# mainpcb.net
KiCad netlist of a schematic drawn in EAGLE
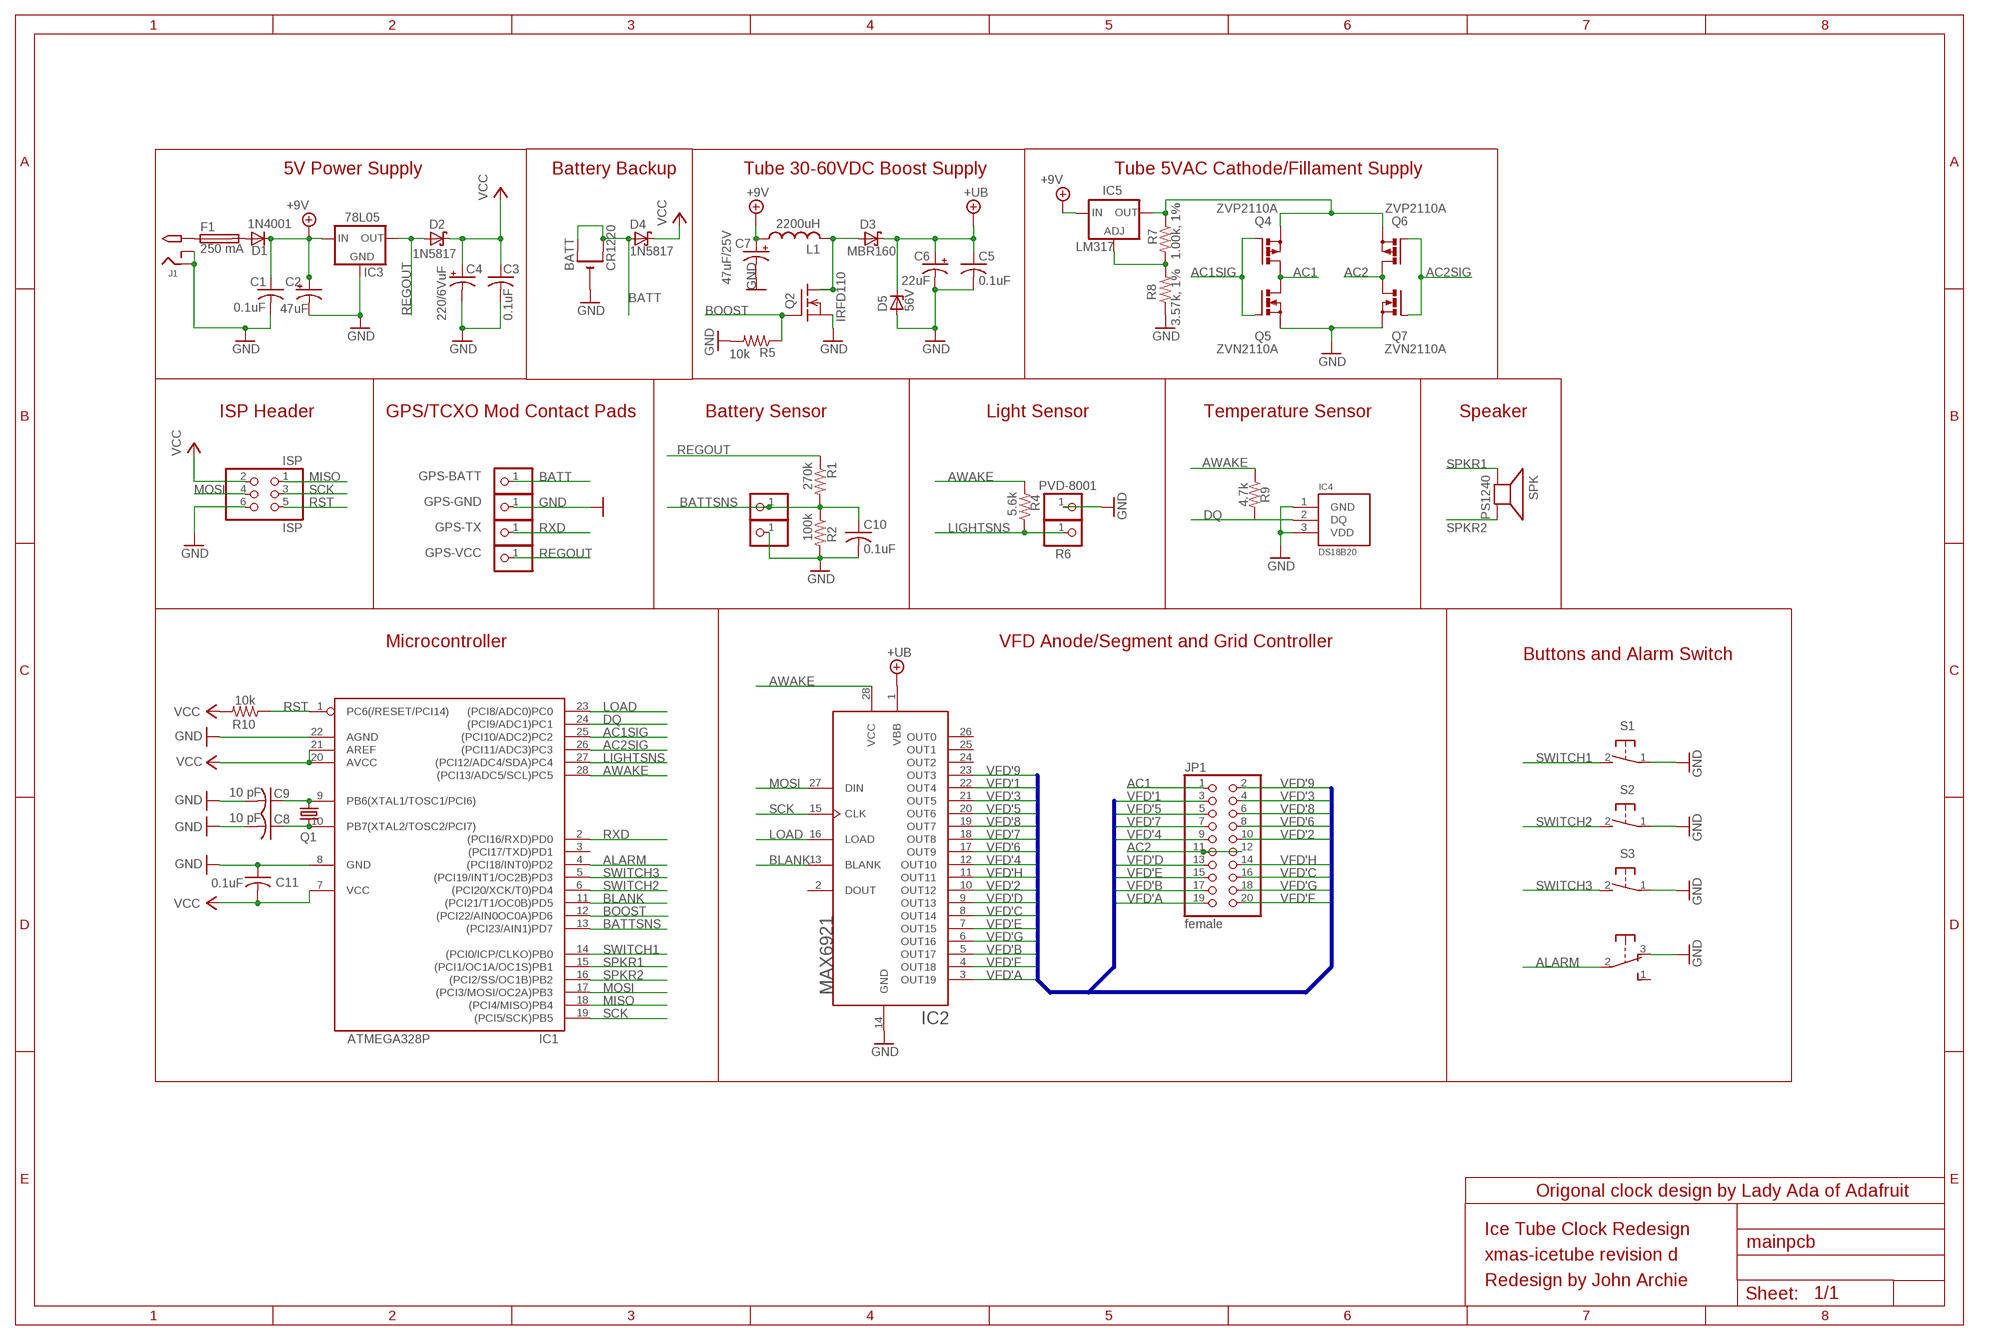
[diagram p0: schematic, sheet 1]

(export (version "E")
  (design (tool "Eeschema 10.0.6"))
  (components
    (comp (ref "BATT")
      (value "CR1220")
      (footprint "eagle-import:CR1220-THM")
      (libsource (lib "eagle-import") (part "CR1220THM"))
    )
    (comp (ref "C1")
      (value "0.1uF")
      (footprint "eagle-import:C025-025X050")
      (libsource (lib "eagle-import") (part "C-US025-025X050"))
    )
    (comp (ref "C2")
      (value "47uF")
      (footprint "eagle-import:E2,5-6")
      (libsource (lib "eagle-import") (part "CPOL-USE2.5-6"))
    )
    (comp (ref "C3")
      (value "0.1uF")
      (footprint "eagle-import:C025-025X050")
      (libsource (lib "eagle-import") (part "C-US025-025X050"))
    )
    (comp (ref "C4")
      (value "220/6VuF")
      (footprint "eagle-import:E2,5-6")
      (libsource (lib "eagle-import") (part "CPOL-USE2.5-6"))
    )
    (comp (ref "C5")
      (value "0.1uF")
      (footprint "eagle-import:C025-024X044")
      (libsource (lib "eagle-import") (part "rcl-ez_C-US025-024X044"))
    )
    (comp (ref "C6")
      (value "22uF")
      (footprint "eagle-import:E3,5-8")
      (libsource (lib "eagle-import") (part "rcl-ez_CPOL-USE3.5-8"))
    )
    (comp (ref "C7")
      (value "47uF/25V")
      (footprint "eagle-import:E2,5-6")
      (libsource (lib "eagle-import") (part "CPOL-USE2.5-6"))
    )
    (comp (ref "C8")
      (value "10 pF")
      (footprint "eagle-import:C025-024X044")
      (libsource (lib "eagle-import") (part "resistor_C-US025-024X044"))
    )
    (comp (ref "C9")
      (value "10 pF")
      (footprint "eagle-import:C025-024X044")
      (libsource (lib "eagle-import") (part "resistor_C-US025-024X044"))
    )
    (comp (ref "C10")
      (value "0.1uF")
      (footprint "eagle-import:C025-024X044")
      (libsource (lib "eagle-import") (part "rcl-ez_C-US025-024X044"))
    )
    (comp (ref "C11")
      (value "0.1uF")
      (footprint "eagle-import:C025-025X050")
      (libsource (lib "eagle-import") (part "C-US025-025X050"))
    )
    (comp (ref "CT2")
      (value "PINHD-1X1")
      (footprint "eagle-import:1X01")
      (libsource (lib "eagle-import") (part "PINHD-1X1"))
    )
    (comp (ref "CT3")
      (value "PINHD-1X1")
      (footprint "eagle-import:1X01")
      (libsource (lib "eagle-import") (part "PINHD-1X1"))
    )
    (comp (ref "D1")
      (value "1N4001")
      (footprint "eagle-import:DO41-10")
      (libsource (lib "eagle-import") (part "1N4004"))
    )
    (comp (ref "D2")
      (value "1N5817")
      (footprint "eagle-import:DO41-10")
      (libsource (lib "eagle-import") (part "SCHOTTKY-DIODEDO41"))
    )
    (comp (ref "D3")
      (value "MBR160")
      (footprint "eagle-import:DO41-10")
      (libsource (lib "eagle-import") (part "SCHOTTKY-DIODEDO41"))
    )
    (comp (ref "D4")
      (value "1N5817")
      (footprint "eagle-import:DO41-10")
      (libsource (lib "eagle-import") (part "SCHOTTKY-DIODEDO41"))
    )
    (comp (ref "D5")
      (value "56V")
      (footprint "eagle-import:DO41Z10")
      (libsource (lib "eagle-import") (part "ZENER-DIODEDO41Z10"))
    )
    (comp (ref "F1")
      (value "250 mA")
      (footprint "eagle-import:TE5")
      (libsource (lib "eagle-import") (part "FUSETE5"))
    )
    (comp (ref "GPS-BATT")
      (value "PINHD-1X1")
      (footprint "eagle-import:1X01")
      (libsource (lib "eagle-import") (part "PINHD-1X1"))
    )
    (comp (ref "GPS-GND")
      (value "PINHD-1X1")
      (footprint "eagle-import:1X01")
      (libsource (lib "eagle-import") (part "PINHD-1X1"))
    )
    (comp (ref "GPS-TX")
      (value "PINHD-1X1")
      (footprint "eagle-import:1X01")
      (libsource (lib "eagle-import") (part "PINHD-1X1"))
    )
    (comp (ref "GPS-VCC")
      (value "PINHD-1X1")
      (footprint "eagle-import:1X01")
      (libsource (lib "eagle-import") (part "PINHD-1X1"))
    )
    (comp (ref "IC1")
      (value "ATMEGA328P")
      (footprint "eagle-import:DIL28_3")
      (libsource (lib "eagle-import") (part "ATMEGA168PROUND"))
    )
    (comp (ref "IC2")
      (value "MAX6921")
      (footprint "eagle-import:PLCC-S28")
      (libsource (lib "eagle-import") (part "MAX6921"))
    )
    (comp (ref "IC3")
      (value "78L05")
      (footprint "eagle-import:TO92-LINE")
      (libsource (lib "eagle-import") (part "78L05"))
    )
    (comp (ref "IC4")
      (value "DS18B20")
      (footprint "eagle-import:TO92")
      (libsource (lib "eagle-import") (part "DS18B20"))
    )
    (comp (ref "IC5")
      (value "LM317")
      (footprint "eagle-import:TO92-LINE")
      (libsource (lib "eagle-import") (part "LM317"))
    )
    (comp (ref "ISP")
      (value "ISP")
      (footprint "eagle-import:2X03")
      (libsource (lib "eagle-import") (part "PINHD-2X3"))
    )
    (comp (ref "J1")
      (value "2.1MMJACK")
      (footprint "eagle-import:PJ-102A")
      (libsource (lib "eagle-import") (part "2.1MMJACK"))
    )
    (comp (ref "JP1")
      (value "female")
      (footprint "eagle-import:2X10")
      (libsource (lib "eagle-import") (part "PINHD-2X10"))
    )
    (comp (ref "L1")
      (value "2200uH")
      (footprint "eagle-import:6000")
      (libsource (lib "eagle-import") (part "L"))
    )
    (comp (ref "Q1")
      (value "32.768 khz")
      (footprint "eagle-import:TC26V")
      (libsource (lib "eagle-import") (part "CRYTALTC26V"))
    )
    (comp (ref "Q2")
      (value "IRFD110")
      (footprint "eagle-import:DIL04")
      (libsource (lib "eagle-import") (part "IRFD110"))
    )
    (comp (ref "Q4")
      (value "ZVP2110A")
      (footprint "eagle-import:TO92-FLAT")
      (libsource (lib "eagle-import") (part "ZVP2110A"))
    )
    (comp (ref "Q5")
      (value "ZVN2110A")
      (footprint "eagle-import:TO92-FLAT")
      (libsource (lib "eagle-import") (part "ZVN2110A"))
    )
    (comp (ref "Q6")
      (value "ZVP2110A")
      (footprint "eagle-import:TO92-FLAT")
      (libsource (lib "eagle-import") (part "ZVP2110A"))
    )
    (comp (ref "Q7")
      (value "ZVN2110A")
      (footprint "eagle-import:TO92-FLAT")
      (libsource (lib "eagle-import") (part "ZVN2110A"))
    )
    (comp (ref "R1")
      (value "270k")
      (footprint "eagle-import:0207_10")
      (libsource (lib "eagle-import") (part "R-US_0207/10"))
    )
    (comp (ref "R2")
      (value "100k")
      (footprint "eagle-import:0207_10")
      (libsource (lib "eagle-import") (part "R-US_0207/10"))
    )
    (comp (ref "R4")
      (value "5.6k")
      (footprint "eagle-import:0207_5V")
      (libsource (lib "eagle-import") (part "R-US_0207/5V"))
    )
    (comp (ref "R5")
      (value "10k")
      (footprint "eagle-import:0207_5V")
      (libsource (lib "eagle-import") (part "R-US_0207/5V"))
    )
    (comp (ref "R6")
      (value "PVD-8001")
      (footprint "eagle-import:1X01")
      (libsource (lib "eagle-import") (part "PINHD-1X1"))
    )
    (comp (ref "R6.1")
      (value "PINHD-1X1")
      (footprint "eagle-import:1X01")
      (libsource (lib "eagle-import") (part "PINHD-1X1"))
    )
    (comp (ref "R7")
      (value "1.00k, 1%")
      (footprint "eagle-import:0207_5V")
      (libsource (lib "eagle-import") (part "R-US_0207/5V"))
    )
    (comp (ref "R8")
      (value "3.57k, 1%")
      (footprint "eagle-import:0207_5V")
      (libsource (lib "eagle-import") (part "R-US_0207/5V"))
    )
    (comp (ref "R9")
      (value "4.7k")
      (footprint "eagle-import:0207_10")
      (libsource (lib "eagle-import") (part "R-US_0207/10"))
    )
    (comp (ref "R10")
      (value "10k")
      (footprint "eagle-import:0207_5V")
      (libsource (lib "eagle-import") (part "R-US_0207/5V"))
    )
    (comp (ref "S1")
      (value "31-XX")
      (footprint "eagle-import:B3F-31XX")
      (libsource (lib "eagle-import") (part "31-XX"))
    )
    (comp (ref "S2")
      (value "31-XX")
      (footprint "eagle-import:B3F-31XX")
      (libsource (lib "eagle-import") (part "31-XX"))
    )
    (comp (ref "S3")
      (value "31-XX")
      (footprint "eagle-import:B3F-31XX")
      (libsource (lib "eagle-import") (part "31-XX"))
    )
    (comp (ref "SPK")
      (value "PS1240")
      (footprint "eagle-import:PS12")
      (libsource (lib "eagle-import") (part "SPEAKER/PS12"))
    )
    (comp (ref "SW1")
      (value "OS102011MA1Q")
      (footprint "eagle-import:OS102011MA1Q")
      (libsource (lib "eagle-import") (part "OS102011MA1Q"))
    )
  )
  (nets
    (net (code "1") (name "+9V") (class "Default")
      (node (ref "C1") (pin "1") (pinfunction "1_1") (pintype "passive"))
      (node (ref "C2") (pin "+") (pinfunction "+_+") (pintype "passive"))
      (node (ref "C7") (pin "+") (pinfunction "+_+") (pintype "passive"))
      (node (ref "D1") (pin "C") (pinfunction "C_C") (pintype "passive"))
      (node (ref "IC3") (pin "3") (pinfunction "IN_3") (pintype "input"))
      (node (ref "IC5") (pin "3") (pinfunction "IN_3") (pintype "input"))
      (node (ref "L1") (pin "1") (pinfunction "1_1") (pintype "passive"))
    )
    (net (code "2") (name "+UB") (class "Default")
      (node (ref "C5") (pin "1") (pinfunction "1_1") (pintype "passive"))
      (node (ref "C6") (pin "+") (pinfunction "+_+") (pintype "passive"))
      (node (ref "D3") (pin "C") (pinfunction "C_C") (pintype "passive"))
      (node (ref "D5") (pin "C") (pinfunction "C_C") (pintype "passive"))
      (node (ref "IC2") (pin "1") (pinfunction "VBB_1") (pintype "power_in"))
    )
    (net (code "3") (name "/AC1") (class "Default")
      (node (ref "JP1") (pin "1") (pinfunction "1_1") (pintype "passive"))
      (node (ref "Q4") (pin "3") (pinfunction "D_3") (pintype "passive"))
      (node (ref "Q5") (pin "3") (pinfunction "D_3") (pintype "passive"))
    )
    (net (code "4") (name "/AC1SIG") (class "Default")
      (node (ref "IC1") (pin "25") (pinfunction "(PCI10/ADC2)PC2_25") (pintype "bidirectional"))
      (node (ref "Q4") (pin "2") (pinfunction "G_2") (pintype "passive"))
      (node (ref "Q5") (pin "2") (pinfunction "G_2") (pintype "passive"))
    )
    (net (code "5") (name "/AC2") (class "Default")
      (node (ref "JP1") (pin "11") (pinfunction "11_11") (pintype "passive"))
      (node (ref "JP1") (pin "12") (pinfunction "12_12") (pintype "passive"))
      (node (ref "Q6") (pin "3") (pinfunction "D_3") (pintype "passive"))
      (node (ref "Q7") (pin "3") (pinfunction "D_3") (pintype "passive"))
    )
    (net (code "6") (name "/AC2SIG") (class "Default")
      (node (ref "IC1") (pin "26") (pinfunction "(PCI11/ADC3)PC3_26") (pintype "bidirectional"))
      (node (ref "Q6") (pin "2") (pinfunction "G_2") (pintype "passive"))
      (node (ref "Q7") (pin "2") (pinfunction "G_2") (pintype "passive"))
    )
    (net (code "7") (name "/ALARM") (class "Default")
      (node (ref "IC1") (pin "4") (pinfunction "(PCI18/INT0)PD2_4") (pintype "bidirectional"))
      (node (ref "SW1") (pin "2") (pinfunction "P_2") (pintype "passive"))
    )
    (net (code "8") (name "/AWAKE") (class "Default")
      (node (ref "IC1") (pin "28") (pinfunction "(PCI13/ADC5/SCL)PC5_28") (pintype "bidirectional"))
      (node (ref "IC2") (pin "28") (pinfunction "VCC_28") (pintype "power_in"))
      (node (ref "R4") (pin "2") (pinfunction "2_2") (pintype "passive"))
      (node (ref "R9") (pin "1") (pinfunction "1_1") (pintype "passive"))
    )
    (net (code "9") (name "/BATT") (class "Default")
      (node (ref "BATT") (pin "+1") (pinfunction "+_+1") (pintype "passive"))
      (node (ref "BATT") (pin "+2") (pinfunction "+1_+2") (pintype "passive"))
      (node (ref "D4") (pin "A") (pinfunction "A_A") (pintype "passive"))
      (node (ref "GPS-BATT") (pin "1") (pinfunction "1_1") (pintype "passive"))
    )
    (net (code "10") (name "/BATTSNS") (class "Default")
      (node (ref "C10") (pin "1") (pinfunction "1_1") (pintype "passive"))
      (node (ref "CT2") (pin "1") (pinfunction "1_1") (pintype "passive"))
      (node (ref "IC1") (pin "13") (pinfunction "(PCI23/AIN1)PD7_13") (pintype "bidirectional"))
      (node (ref "R1") (pin "2") (pinfunction "2_2") (pintype "passive"))
      (node (ref "R2") (pin "1") (pinfunction "1_1") (pintype "passive"))
    )
    (net (code "11") (name "/BLANK") (class "Default")
      (node (ref "IC1") (pin "11") (pinfunction "(PCI21/T1/OC0B)PD5_11") (pintype "bidirectional"))
      (node (ref "IC2") (pin "13") (pinfunction "BLANK_13") (pintype "input"))
    )
    (net (code "12") (name "/BOOST") (class "Default")
      (node (ref "IC1") (pin "12") (pinfunction "(PCI22/AIN0OC0A)PD6_12") (pintype "bidirectional"))
      (node (ref "Q2") (pin "3") (pinfunction "G_3") (pintype "passive"))
      (node (ref "R5") (pin "1") (pinfunction "1_1") (pintype "passive"))
    )
    (net (code "13") (name "/DQ") (class "Default")
      (node (ref "IC1") (pin "24") (pinfunction "(PCI9/ADC1)PC1_24") (pintype "bidirectional"))
      (node (ref "IC4") (pin "2") (pinfunction "DQ_2") (pintype "bidirectional"))
      (node (ref "R9") (pin "2") (pinfunction "2_2") (pintype "passive"))
    )
    (net (code "14") (name "/LIGHTSNS") (class "Default")
      (node (ref "IC1") (pin "27") (pinfunction "(PCI12/ADC4/SDA)PC4_27") (pintype "bidirectional"))
      (node (ref "R4") (pin "1") (pinfunction "1_1") (pintype "passive"))
      (node (ref "R6.1") (pin "1") (pinfunction "1_1") (pintype "passive"))
    )
    (net (code "15") (name "/LOAD") (class "Default")
      (node (ref "IC1") (pin "23") (pinfunction "(PCI8/ADC0)PC0_23") (pintype "bidirectional"))
      (node (ref "IC2") (pin "16") (pinfunction "LOAD_16") (pintype "input"))
    )
    (net (code "16") (name "/MISO") (class "Default")
      (node (ref "IC1") (pin "18") (pinfunction "(PCI4/MISO)PB4_18") (pintype "bidirectional"))
      (node (ref "ISP") (pin "1") (pinfunction "1_1") (pintype "passive"))
    )
    (net (code "17") (name "/MOSI") (class "Default")
      (node (ref "IC1") (pin "17") (pinfunction "(PCI3/MOSI/OC2A)PB3_17") (pintype "bidirectional"))
      (node (ref "IC2") (pin "27") (pinfunction "DIN_27") (pintype "input"))
      (node (ref "ISP") (pin "4") (pinfunction "4_4") (pintype "passive"))
    )
    (net (code "18") (name "/REGOUT") (class "Default")
      (node (ref "D2") (pin "A") (pinfunction "A_A") (pintype "passive"))
      (node (ref "GPS-VCC") (pin "1") (pinfunction "1_1") (pintype "passive"))
      (node (ref "IC3") (pin "1") (pinfunction "OUT_1") (pintype "passive"))
      (node (ref "R1") (pin "1") (pinfunction "1_1") (pintype "passive"))
    )
    (net (code "19") (name "/RST") (class "Default")
      (node (ref "IC1") (pin "1") (pinfunction "PC6(/RESET/PCI14)_1") (pintype "bidirectional"))
      (node (ref "ISP") (pin "5") (pinfunction "5_5") (pintype "passive"))
      (node (ref "R10") (pin "1") (pinfunction "1_1") (pintype "passive"))
    )
    (net (code "20") (name "/RXD") (class "Default")
      (node (ref "GPS-TX") (pin "1") (pinfunction "1_1") (pintype "passive"))
      (node (ref "IC1") (pin "2") (pinfunction "(PCI16/RXD)PD0_2") (pintype "bidirectional"))
    )
    (net (code "21") (name "/SCK") (class "Default")
      (node (ref "IC1") (pin "19") (pinfunction "(PCI5/SCK)PB5_19") (pintype "bidirectional"))
      (node (ref "IC2") (pin "15") (pinfunction "CLK_15") (pintype "input"))
      (node (ref "ISP") (pin "3") (pinfunction "3_3") (pintype "passive"))
    )
    (net (code "22") (name "/SPKR1") (class "Default")
      (node (ref "IC1") (pin "15") (pinfunction "(PCI1/OC1A/OC1S)PB1_15") (pintype "bidirectional"))
      (node (ref "SPK") (pin "P$1") (pinfunction "+_P$1") (pintype "passive"))
    )
    (net (code "23") (name "/SPKR2") (class "Default")
      (node (ref "IC1") (pin "16") (pinfunction "(PCI2/SS/OC1B)PB2_16") (pintype "bidirectional"))
      (node (ref "SPK") (pin "P$2") (pinfunction "-_P$2") (pintype "passive"))
    )
    (net (code "24") (name "/SWITCH1") (class "Default")
      (node (ref "IC1") (pin "14") (pinfunction "(PCI0/ICP/CLKO)PB0_14") (pintype "bidirectional"))
      (node (ref "S1") (pin "2") (pinfunction "S_2") (pintype "passive"))
    )
    (net (code "25") (name "/SWITCH2") (class "Default")
      (node (ref "IC1") (pin "6") (pinfunction "(PCI20/XCK/T0)PD4_6") (pintype "bidirectional"))
      (node (ref "S2") (pin "2") (pinfunction "S_2") (pintype "passive"))
    )
    (net (code "26") (name "/SWITCH3") (class "Default")
      (node (ref "IC1") (pin "5") (pinfunction "(PCI19/INT1/OC2B)PD3_5") (pintype "bidirectional"))
      (node (ref "S3") (pin "2") (pinfunction "S_2") (pintype "passive"))
    )
    (net (code "27") (name "/VFD'1") (class "Default")
      (node (ref "IC2") (pin "22") (pinfunction "OUT4_22") (pintype "output"))
      (node (ref "JP1") (pin "3") (pinfunction "3_3") (pintype "passive"))
    )
    (net (code "28") (name "/VFD'2") (class "Default")
      (node (ref "IC2") (pin "10") (pinfunction "OUT12_10") (pintype "output"))
      (node (ref "JP1") (pin "10") (pinfunction "10_10") (pintype "passive"))
    )
    (net (code "29") (name "/VFD'3") (class "Default")
      (node (ref "IC2") (pin "21") (pinfunction "OUT5_21") (pintype "output"))
      (node (ref "JP1") (pin "4") (pinfunction "4_4") (pintype "passive"))
    )
    (net (code "30") (name "/VFD'4") (class "Default")
      (node (ref "IC2") (pin "12") (pinfunction "OUT10_12") (pintype "output"))
      (node (ref "JP1") (pin "9") (pinfunction "9_9") (pintype "passive"))
    )
    (net (code "31") (name "/VFD'5") (class "Default")
      (node (ref "IC2") (pin "20") (pinfunction "OUT6_20") (pintype "output"))
      (node (ref "JP1") (pin "5") (pinfunction "5_5") (pintype "passive"))
    )
    (net (code "32") (name "/VFD'6") (class "Default")
      (node (ref "IC2") (pin "17") (pinfunction "OUT9_17") (pintype "output"))
      (node (ref "JP1") (pin "8") (pinfunction "8_8") (pintype "passive"))
    )
    (net (code "33") (name "/VFD'7") (class "Default")
      (node (ref "IC2") (pin "18") (pinfunction "OUT8_18") (pintype "output"))
      (node (ref "JP1") (pin "7") (pinfunction "7_7") (pintype "passive"))
    )
    (net (code "34") (name "/VFD'8") (class "Default")
      (node (ref "IC2") (pin "19") (pinfunction "OUT7_19") (pintype "output"))
      (node (ref "JP1") (pin "6") (pinfunction "6_6") (pintype "passive"))
    )
    (net (code "35") (name "/VFD'9") (class "Default")
      (node (ref "IC2") (pin "23") (pinfunction "OUT3_23") (pintype "output"))
      (node (ref "JP1") (pin "2") (pinfunction "2_2") (pintype "passive"))
    )
    (net (code "36") (name "/VFD'A") (class "Default")
      (node (ref "IC2") (pin "3") (pinfunction "OUT19_3") (pintype "output"))
      (node (ref "JP1") (pin "19") (pinfunction "19_19") (pintype "passive"))
    )
    (net (code "37") (name "/VFD'B") (class "Default")
      (node (ref "IC2") (pin "5") (pinfunction "OUT17_5") (pintype "output"))
      (node (ref "JP1") (pin "17") (pinfunction "17_17") (pintype "passive"))
    )
    (net (code "38") (name "/VFD'C") (class "Default")
      (node (ref "IC2") (pin "8") (pinfunction "OUT14_8") (pintype "output"))
      (node (ref "JP1") (pin "16") (pinfunction "16_16") (pintype "passive"))
    )
    (net (code "39") (name "/VFD'D") (class "Default")
      (node (ref "IC2") (pin "9") (pinfunction "OUT13_9") (pintype "output"))
      (node (ref "JP1") (pin "13") (pinfunction "13_13") (pintype "passive"))
    )
    (net (code "40") (name "/VFD'E") (class "Default")
      (node (ref "IC2") (pin "7") (pinfunction "OUT15_7") (pintype "output"))
      (node (ref "JP1") (pin "15") (pinfunction "15_15") (pintype "passive"))
    )
    (net (code "41") (name "/VFD'F") (class "Default")
      (node (ref "IC2") (pin "4") (pinfunction "OUT18_4") (pintype "output"))
      (node (ref "JP1") (pin "20") (pinfunction "20_20") (pintype "passive"))
    )
    (net (code "42") (name "/VFD'G") (class "Default")
      (node (ref "IC2") (pin "6") (pinfunction "OUT16_6") (pintype "output"))
      (node (ref "JP1") (pin "18") (pinfunction "18_18") (pintype "passive"))
    )
    (net (code "43") (name "/VFD'H") (class "Default")
      (node (ref "IC2") (pin "11") (pinfunction "OUT11_11") (pintype "output"))
      (node (ref "JP1") (pin "14") (pinfunction "14_14") (pintype "passive"))
    )
    (net (code "44") (name "GND") (class "Default")
      (node (ref "BATT") (pin "-") (pinfunction "-_-") (pintype "passive"))
      (node (ref "C1") (pin "2") (pinfunction "2_2") (pintype "passive"))
      (node (ref "C10") (pin "2") (pinfunction "2_2") (pintype "passive"))
      (node (ref "C11") (pin "1") (pinfunction "1_1") (pintype "passive"))
      (node (ref "C2") (pin "-") (pinfunction "-_-") (pintype "passive"))
      (node (ref "C3") (pin "2") (pinfunction "2_2") (pintype "passive"))
      (node (ref "C4") (pin "-") (pinfunction "-_-") (pintype "passive"))
      (node (ref "C5") (pin "2") (pinfunction "2_2") (pintype "passive"))
      (node (ref "C6") (pin "-") (pinfunction "-_-") (pintype "passive"))
      (node (ref "C7") (pin "-") (pinfunction "-_-") (pintype "passive"))
      (node (ref "C8") (pin "2") (pinfunction "2_2") (pintype "passive"))
      (node (ref "C9") (pin "2") (pinfunction "2_2") (pintype "passive"))
      (node (ref "CT3") (pin "1") (pinfunction "1_1") (pintype "passive"))
      (node (ref "D5") (pin "A") (pinfunction "A_A") (pintype "passive"))
      (node (ref "GPS-GND") (pin "1") (pinfunction "1_1") (pintype "passive"))
      (node (ref "IC1") (pin "22") (pinfunction "AGND_22") (pintype "bidirectional"))
      (node (ref "IC1") (pin "8") (pinfunction "GND_8") (pintype "bidirectional"))
      (node (ref "IC2") (pin "14") (pinfunction "GND_14") (pintype "power_in"))
      (node (ref "IC3") (pin "2") (pinfunction "GND_2") (pintype "input"))
      (node (ref "IC4") (pin "1") (pinfunction "GND_1") (pintype "bidirectional"))
      (node (ref "IC4") (pin "3") (pinfunction "VDD_3") (pintype "bidirectional"))
      (node (ref "ISP") (pin "6") (pinfunction "6_6") (pintype "passive"))
      (node (ref "J1") (pin "RING") (pinfunction "RING_RING") (pintype "bidirectional"))
      (node (ref "J1") (pin "RING_SW") (pinfunction "RING_SW_RING_SW") (pintype "bidirectional"))
      (node (ref "Q2") (pin "4") (pinfunction "S_4") (pintype "passive"))
      (node (ref "Q5") (pin "1") (pinfunction "S_1") (pintype "passive"))
      (node (ref "Q7") (pin "1") (pinfunction "S_1") (pintype "passive"))
      (node (ref "R2") (pin "2") (pinfunction "2_2") (pintype "passive"))
      (node (ref "R5") (pin "2") (pinfunction "2_2") (pintype "passive"))
      (node (ref "R6") (pin "1") (pinfunction "1_1") (pintype "passive"))
      (node (ref "R8") (pin "1") (pinfunction "1_1") (pintype "passive"))
      (node (ref "S1") (pin "1") (pinfunction "P_1") (pintype "passive"))
      (node (ref "S2") (pin "1") (pinfunction "P_1") (pintype "passive"))
      (node (ref "S3") (pin "1") (pinfunction "P_1") (pintype "passive"))
      (node (ref "SW1") (pin "3") (pinfunction "O_3") (pintype "passive"))
    )
    (net (code "45") (name "Net-(D1-PadA)") (class "Default")
      (node (ref "D1") (pin "A") (pinfunction "A_A") (pintype "passive"))
      (node (ref "F1") (pin "2") (pinfunction "2_2") (pintype "passive"))
    )
    (net (code "46") (name "Net-(F1-Pad1)") (class "Default")
      (node (ref "F1") (pin "1") (pinfunction "1_1") (pintype "passive"))
      (node (ref "J1") (pin "TIP") (pinfunction "TIP_TIP") (pintype "bidirectional"))
    )
    (net (code "47") (name "Net-(IC1-PB6(XTAL1{slash}TOSC1{slash}PCI6))") (class "Default")
      (node (ref "C9") (pin "1") (pinfunction "1_1") (pintype "passive"))
      (node (ref "IC1") (pin "9") (pinfunction "PB6(XTAL1/TOSC1/PCI6)_9") (pintype "bidirectional"))
      (node (ref "Q1") (pin "2") (pinfunction "2_2") (pintype "passive"))
    )
    (net (code "48") (name "Net-(IC1-PB7(XTAL2{slash}TOSC2{slash}PCI7))") (class "Default")
      (node (ref "C8") (pin "1") (pinfunction "1_1") (pintype "passive"))
      (node (ref "IC1") (pin "10") (pinfunction "PB7(XTAL2/TOSC2/PCI7)_10") (pintype "bidirectional"))
      (node (ref "Q1") (pin "1") (pinfunction "1_1") (pintype "passive"))
    )
    (net (code "49") (name "Net-(IC5-ADJ)") (class "Default")
      (node (ref "IC5") (pin "1") (pinfunction "ADJ_1") (pintype "input"))
      (node (ref "R7") (pin "2") (pinfunction "2_2") (pintype "passive"))
      (node (ref "R8") (pin "2") (pinfunction "2_2") (pintype "passive"))
    )
    (net (code "50") (name "Net-(IC5-OUT)") (class "Default")
      (node (ref "IC5") (pin "2") (pinfunction "OUT_2") (pintype "passive"))
      (node (ref "Q4") (pin "1") (pinfunction "S_1") (pintype "passive"))
      (node (ref "Q6") (pin "1") (pinfunction "S_1") (pintype "passive"))
      (node (ref "R7") (pin "1") (pinfunction "1_1") (pintype "passive"))
    )
    (net (code "51") (name "Net-(Q2-D)") (class "Default")
      (node (ref "D3") (pin "A") (pinfunction "A_A") (pintype "passive"))
      (node (ref "L1") (pin "2") (pinfunction "2_2") (pintype "passive"))
      (node (ref "Q2") (pin "1") (pinfunction "D_1") (pintype "passive"))
      (node (ref "Q2") (pin "2") (pinfunction "D1_2") (pintype "passive"))
    )
    (net (code "52") (name "VCC") (class "Default")
      (node (ref "C11") (pin "2") (pinfunction "2_2") (pintype "passive"))
      (node (ref "C3") (pin "1") (pinfunction "1_1") (pintype "passive"))
      (node (ref "C4") (pin "+") (pinfunction "+_+") (pintype "passive"))
      (node (ref "D2") (pin "C") (pinfunction "C_C") (pintype "passive"))
      (node (ref "D4") (pin "C") (pinfunction "C_C") (pintype "passive"))
      (node (ref "IC1") (pin "20") (pinfunction "AVCC_20") (pintype "bidirectional"))
      (node (ref "IC1") (pin "21") (pinfunction "AREF_21") (pintype "bidirectional"))
      (node (ref "IC1") (pin "7") (pinfunction "VCC_7") (pintype "bidirectional"))
      (node (ref "ISP") (pin "2") (pinfunction "2_2") (pintype "passive"))
      (node (ref "R10") (pin "2") (pinfunction "2_2") (pintype "passive"))
    )
    (net (code "53") (name "unconnected-(IC1-(PCI17{slash}TXD)PD1-Pad3)") (class "Default")
      (node (ref "IC1") (pin "3") (pinfunction "(PCI17/TXD)PD1_3") (pintype "bidirectional"))
    )
    (net (code "54") (name "unconnected-(IC2-DOUT-Pad2)") (class "Default")
      (node (ref "IC2") (pin "2") (pinfunction "DOUT_2") (pintype "output"))
    )
    (net (code "55") (name "unconnected-(IC2-OUT0-Pad26)") (class "Default")
      (node (ref "IC2") (pin "26") (pinfunction "OUT0_26") (pintype "output"))
    )
    (net (code "56") (name "unconnected-(IC2-OUT1-Pad25)") (class "Default")
      (node (ref "IC2") (pin "25") (pinfunction "OUT1_25") (pintype "output"))
    )
    (net (code "57") (name "unconnected-(IC2-OUT2-Pad24)") (class "Default")
      (node (ref "IC2") (pin "24") (pinfunction "OUT2_24") (pintype "output"))
    )
    (net (code "58") (name "unconnected-(SW1A-S-Pad1)") (class "Default")
      (node (ref "SW1") (pin "1") (pinfunction "S_1") (pintype "passive"))
    )
  )
)
